# microcontrollerOptical.net
KiCad netlist of a schematic drawn in Altium Designer
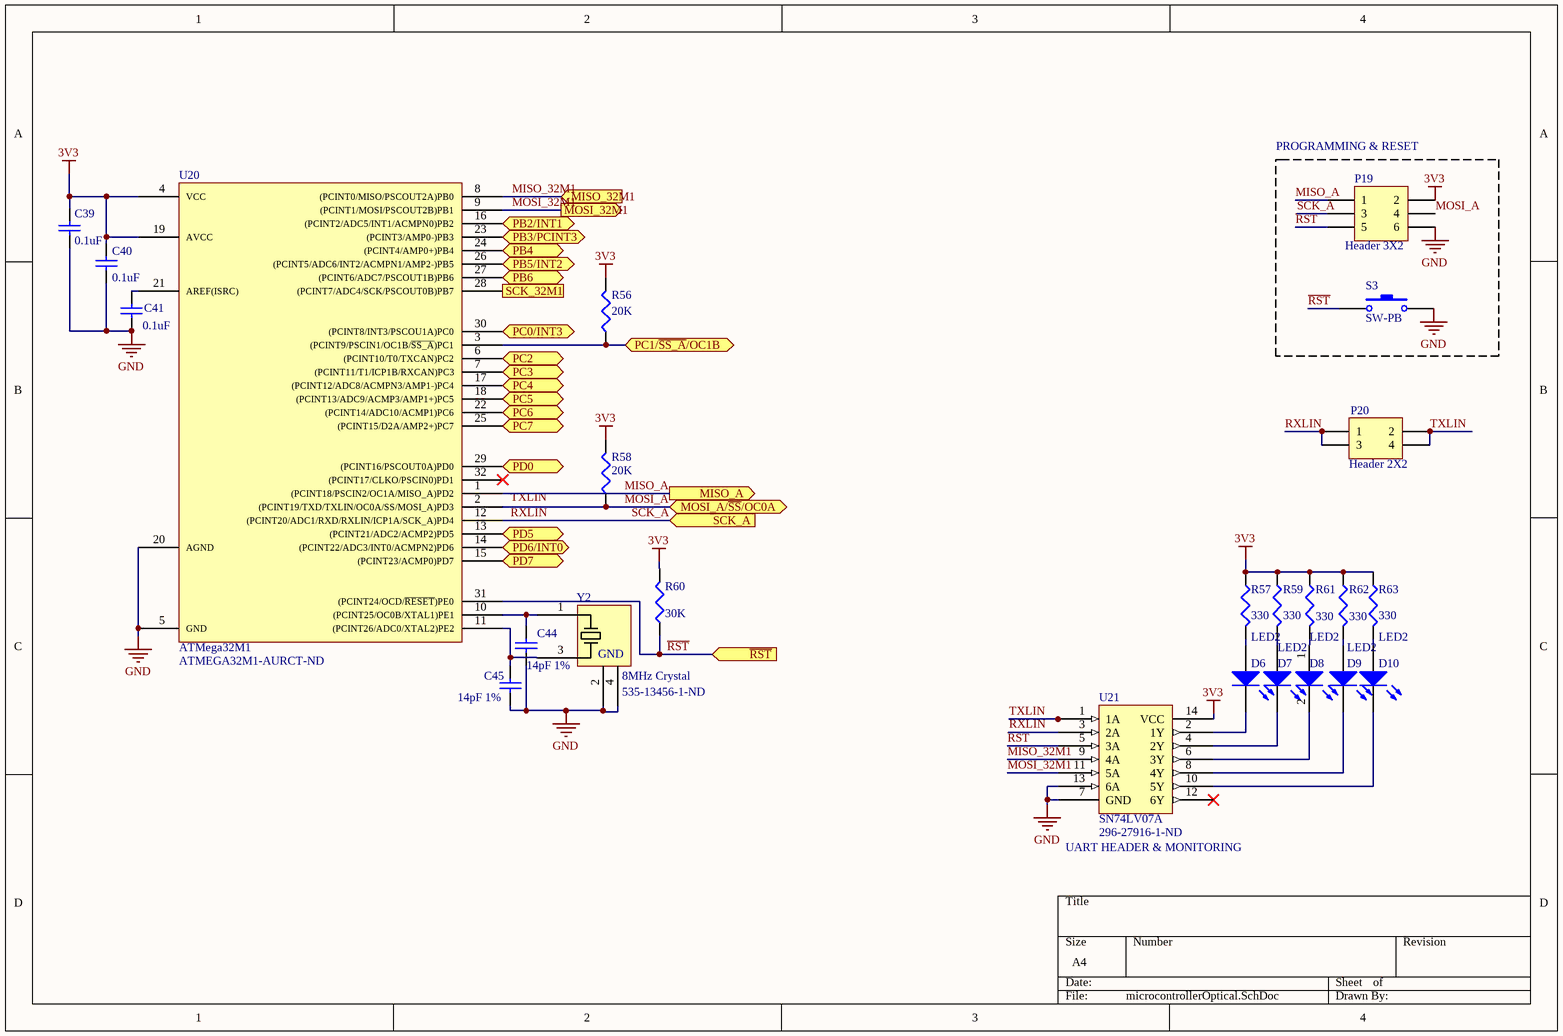
[diagram p0: microcontrollerOptical.SchDoc]

(export (version "E")
  (design (tool "Eeschema 10.0.6"))
  (components
    (comp (ref "C39")
      (value "0.1uF")
      (footprint "1608[0603]")
      (description "Capacitor (Semiconductor SIM Model)")
      (fields (field (name "PUBLISHER") "Altium Limited"))
      (libsource (lib "Miscellaneous Devices") (part "Cap Semi"))
    )
    (comp (ref "C40")
      (value "0.1uF")
      (footprint "1608[0603]")
      (description "Capacitor (Semiconductor SIM Model)")
      (fields (field (name "PUBLISHER") "Altium Limited"))
      (libsource (lib "Miscellaneous Devices") (part "Cap Semi"))
    )
    (comp (ref "C41")
      (value "0.1uF")
      (footprint "1608[0603]")
      (description "Capacitor (Semiconductor SIM Model)")
      (fields (field (name "PUBLISHER") "Altium Limited"))
      (libsource (lib "Miscellaneous Devices") (part "Cap Semi"))
    )
    (comp (ref "C44")
      (value "14pF 1%")
      (footprint "1608[0603]")
      (description "Capacitor (Semiconductor SIM Model)")
      (fields (field (name "Comment") "15pF 1%") (field (name "PUBLISHER") "Altium Limited"))
      (libsource (lib "Miscellaneous Devices") (part "Cap Semi"))
    )
    (comp (ref "C45")
      (value "14pF 1%")
      (footprint "1608[0603]")
      (description "Capacitor (Semiconductor SIM Model)")
      (fields (field (name "Comment") "15pF 1%") (field (name "PUBLISHER") "Altium Limited"))
      (libsource (lib "Miscellaneous Devices") (part "Cap Semi"))
    )
    (comp (ref "D6")
      (value "LED2")
      (footprint "0603-LED")
      (description "Typical RED, GREEN, YELLOW, AMBER GaAs LED")
      (fields (field (name "PUBLISHER") "Altium Limited"))
      (libsource (lib "Miscellaneous Devices") (part "LED2"))
    )
    (comp (ref "D7")
      (value "LED2")
      (footprint "0603-LED")
      (description "Typical RED, GREEN, YELLOW, AMBER GaAs LED")
      (fields (field (name "PUBLISHER") "Altium Limited"))
      (libsource (lib "Miscellaneous Devices") (part "LED2"))
    )
    (comp (ref "D8")
      (value "LED2")
      (footprint "0603-LED")
      (description "Typical RED, GREEN, YELLOW, AMBER GaAs LED")
      (fields (field (name "PUBLISHER") "Altium Limited"))
      (libsource (lib "") (part "LED2_1"))
    )
    (comp (ref "D9")
      (value "LED2")
      (footprint "0603-LED")
      (description "Typical RED, GREEN, YELLOW, AMBER GaAs LED")
      (fields (field (name "PUBLISHER") "Altium Limited"))
      (libsource (lib "Miscellaneous Devices") (part "LED2"))
    )
    (comp (ref "D10")
      (value "LED2")
      (footprint "0603-LED")
      (description "Typical RED, GREEN, YELLOW, AMBER GaAs LED")
      (fields (field (name "PUBLISHER") "Altium Limited"))
      (libsource (lib "Miscellaneous Devices") (part "LED2"))
    )
    (comp (ref "P19")
      (value "Header 3X2")
      (footprint "HDR2X3")
      (description "Header, 3-Pin, Dual row")
      (fields (field (name "PUBLISHER") "Altium Limited"))
      (libsource (lib "Miscellaneous Connectors") (part "Header 3X2"))
    )
    (comp (ref "P20")
      (value "Header 2X2")
      (footprint "HDR2X2")
      (description "Header, 2-Pin, Dual row")
      (fields (field (name "PUBLISHER") "Altium Limited"))
      (libsource (lib "Miscellaneous Connectors") (part "Header 2X2"))
    )
    (comp (ref "R56")
      (value "20K")
      (footprint "J1-0603")
      (description "Resistor")
      (fields (field (name "PUBLISHER") "Altium Limited"))
      (libsource (lib "Miscellaneous Devices") (part "Res3"))
    )
    (comp (ref "R57")
      (value "330")
      (footprint "J1-0603")
      (description "Resistor")
      (fields (field (name "PUBLISHER") "Altium Limited"))
      (libsource (lib "Miscellaneous Devices") (part "Res3"))
    )
    (comp (ref "R58")
      (value "20K")
      (footprint "J1-0603")
      (description "Resistor")
      (fields (field (name "PUBLISHER") "Altium Limited"))
      (libsource (lib "Miscellaneous Devices") (part "Res3"))
    )
    (comp (ref "R59")
      (value "330")
      (footprint "J1-0603")
      (description "Resistor")
      (fields (field (name "PUBLISHER") "Altium Limited"))
      (libsource (lib "Miscellaneous Devices") (part "Res3"))
    )
    (comp (ref "R60")
      (value "30K")
      (footprint "J1-0603")
      (description "Resistor")
      (fields (field (name "PUBLISHER") "Altium Limited"))
      (libsource (lib "Miscellaneous Devices") (part "Res3"))
    )
    (comp (ref "R61")
      (value "330")
      (footprint "J1-0603")
      (description "Resistor")
      (fields (field (name "PUBLISHER") "Altium Limited"))
      (libsource (lib "Miscellaneous Devices") (part "Res3"))
    )
    (comp (ref "R62")
      (value "330")
      (footprint "J1-0603")
      (description "Resistor")
      (fields (field (name "PUBLISHER") "Altium Limited"))
      (libsource (lib "Miscellaneous Devices") (part "Res3"))
    )
    (comp (ref "R63")
      (value "330")
      (footprint "J1-0603")
      (description "Resistor")
      (fields (field (name "PUBLISHER") "Altium Limited"))
      (libsource (lib "Miscellaneous Devices") (part "Res3"))
    )
    (comp (ref "S3")
      (value "SW-PB")
      (footprint "Pushbutton")
      (description "Switch")
      (fields (field (name "PUBLISHER") "Altium Limited"))
      (libsource (lib "Miscellaneous Devices") (part "SW-PB"))
    )
    (comp (ref "U20")
      (value "ATMega32M1")
      (footprint "QFP80P900X900X120-32N")
      (description "Atmel 8-bit AVR microcontroller.")
      (fields (field (name "SUPPLIER PART NUMBER 1") "ATMEGA32M1-AURCT-ND"))
      (libsource (lib "ICs") (part "ATMega32M1"))
    )
    (comp (ref "U21")
      (value "SN74LV07A")
      (footprint "SOP65P640X120-14N")
      (description "Six element 1-bit non-inverting open-drain buffer.")
      (fields (field (name "SUPPLIER PART NUMBER") "296-27916-1-ND"))
      (libsource (lib "ICs") (part "SN74LV07A"))
    )
    (comp (ref "Y2")
      (value "8MHz Crystal")
      (footprint "OSCSC500X320X110-4N")
      (description "8MHz Abracom 4-pin crystal.")
      (fields (field (name "SUPPLIER PART NUMBER 1") "535-13456-1-ND"))
      (libsource (lib "ICs") (part "8MHz Abracom 4-Pin Crystal"))
    )
  )
  (nets
    (net (code "1") (name "/MISO_32M1") (class "Default")
      (node (ref "U20") (pin "8") (pinfunction "(PCINT0/MISO/PSCOUT2A)PB0_8") (pintype "passive"))
      (node (ref "U21") (pin "9") (pinfunction "4A_9") (pintype "input"))
    )
    (net (code "2") (name "/MISO_A") (class "Default")
      (node (ref "P19") (pin "1") (pinfunction "1_1") (pintype "passive"))
      (node (ref "U20") (pin "1") (pinfunction "(PCINT18/PSCIN2/OC1A/MISO_A)PD2_1") (pintype "passive"))
    )
    (net (code "3") (name "/MOSI_32M1") (class "Default")
      (node (ref "U20") (pin "9") (pinfunction "(PCINT1/MOSI/PSCOUT2B)PB1_9") (pintype "passive"))
      (node (ref "U21") (pin "11") (pinfunction "5A_11") (pintype "input"))
    )
    (net (code "4") (name "/MOSI_A") (class "Default")
      (node (ref "P19") (pin "4") (pinfunction "4_4") (pintype "passive"))
      (node (ref "R58") (pin "1") (pinfunction "1_1") (pintype "passive"))
      (node (ref "U20") (pin "2") (pinfunction "(PCINT19/TXD/TXLIN/OC0A/SS/MOSI_A)PD3_2") (pintype "passive"))
    )
    (net (code "5") (name "/PB2{slash}INT1") (class "Default")
      (node (ref "U20") (pin "16") (pinfunction "(PCINT2/ADC5/INT1/ACMPN0)PB2_16") (pintype "passive"))
    )
    (net (code "6") (name "/PB3{slash}PCINT3") (class "Default")
      (node (ref "U20") (pin "23") (pinfunction "(PCINT3/AMP0-)PB3_23") (pintype "passive"))
    )
    (net (code "7") (name "/PB4") (class "Default")
      (node (ref "U20") (pin "24") (pinfunction "(PCINT4/AMP0+)PB4_24") (pintype "passive"))
    )
    (net (code "8") (name "/PB5{slash}INT2") (class "Default")
      (node (ref "U20") (pin "26") (pinfunction "(PCINT5/ADC6/INT2/ACMPN1/AMP2-)PB5_26") (pintype "passive"))
    )
    (net (code "9") (name "/PB6") (class "Default")
      (node (ref "U20") (pin "27") (pinfunction "(PCINT6/ADC7/PSCOUT1B)PB6_27") (pintype "passive"))
    )
    (net (code "10") (name "/PC0{slash}INT3") (class "Default")
      (node (ref "U20") (pin "30") (pinfunction "(PCINT8/INT3/PSCOU1A)PC0_30") (pintype "passive"))
    )
    (net (code "11") (name "/PC1{slash}~{SS_A}{slash}OC1B") (class "Default")
      (node (ref "R56") (pin "1") (pinfunction "1_1") (pintype "passive"))
      (node (ref "U20") (pin "3") (pinfunction "(PCINT9/PSCIN1/OC1B/~{SS_A})PC1_3") (pintype "passive"))
    )
    (net (code "12") (name "/PC2") (class "Default")
      (node (ref "U20") (pin "6") (pinfunction "(PCINT10/T0/TXCAN)PC2_6") (pintype "passive"))
    )
    (net (code "13") (name "/PC3") (class "Default")
      (node (ref "U20") (pin "7") (pinfunction "(PCINT11/T1/ICP1B/RXCAN)PC3_7") (pintype "passive"))
    )
    (net (code "14") (name "/PC4") (class "Default")
      (node (ref "U20") (pin "17") (pinfunction "(PCINT12/ADC8/ACMPN3/AMP1-)PC4_17") (pintype "passive"))
    )
    (net (code "15") (name "/PC5") (class "Default")
      (node (ref "U20") (pin "18") (pinfunction "(PCINT13/ADC9/ACMP3/AMP1+)PC5_18") (pintype "passive"))
    )
    (net (code "16") (name "/PC6") (class "Default")
      (node (ref "U20") (pin "22") (pinfunction "(PCINT14/ADC10/ACMP1)PC6_22") (pintype "passive"))
    )
    (net (code "17") (name "/PC7") (class "Default")
      (node (ref "U20") (pin "25") (pinfunction "(PCINT15/D2A/AMP2+)PC7_25") (pintype "passive"))
    )
    (net (code "18") (name "/PD0") (class "Default")
      (node (ref "U20") (pin "29") (pinfunction "(PCINT16/PSCOUT0A)PD0_29") (pintype "passive"))
    )
    (net (code "19") (name "/PD5") (class "Default")
      (node (ref "U20") (pin "13") (pinfunction "(PCINT21/ADC2/ACMP2)PD5_13") (pintype "passive"))
    )
    (net (code "20") (name "/PD6{slash}INT0") (class "Default")
      (node (ref "U20") (pin "14") (pinfunction "(PCINT22/ADC3/INT0/ACMPN2)PD6_14") (pintype "passive"))
    )
    (net (code "21") (name "/PD7") (class "Default")
      (node (ref "U20") (pin "15") (pinfunction "(PCINT23/ACMP0)PD7_15") (pintype "passive"))
    )
    (net (code "22") (name "/RXLIN") (class "Default")
      (node (ref "P19") (pin "3") (pinfunction "3_3") (pintype "passive"))
      (node (ref "P20") (pin "1") (pinfunction "1_1") (pintype "passive"))
      (node (ref "P20") (pin "3") (pinfunction "3_3") (pintype "passive"))
      (node (ref "U20") (pin "12") (pinfunction "(PCINT20/ADC1/RXD/RXLIN/ICP1A/SCK_A)PD4_12") (pintype "passive"))
      (node (ref "U21") (pin "3") (pinfunction "2A_3") (pintype "input"))
    )
    (net (code "23") (name "/SCK_32M1") (class "Default")
      (node (ref "U20") (pin "28") (pinfunction "(PCINT7/ADC4/SCK/PSCOUT0B)PB7_28") (pintype "passive"))
    )
    (net (code "24") (name "/TXLIN") (class "Default")
      (node (ref "P20") (pin "2") (pinfunction "2_2") (pintype "passive"))
      (node (ref "P20") (pin "4") (pinfunction "4_4") (pintype "passive"))
      (node (ref "U21") (pin "1") (pinfunction "1A_1") (pintype "input"))
    )
    (net (code "25") (name "/~{RST}") (class "Default")
      (node (ref "P19") (pin "5") (pinfunction "5_5") (pintype "passive"))
      (node (ref "R60") (pin "1") (pinfunction "1_1") (pintype "passive"))
      (node (ref "S3") (pin "1") (pinfunction "1_1") (pintype "passive"))
      (node (ref "U20") (pin "31") (pinfunction "(PCINT24/OCD/~{RESET})PE0_31") (pintype "passive"))
      (node (ref "U21") (pin "5") (pinfunction "3A_5") (pintype "input"))
    )
    (net (code "26") (name "3V3") (class "Default")
      (node (ref "C39") (pin "2") (pinfunction "2_2") (pintype "passive"))
      (node (ref "C40") (pin "2") (pinfunction "2_2") (pintype "passive"))
      (node (ref "P19") (pin "2") (pinfunction "2_2") (pintype "passive"))
      (node (ref "R56") (pin "2") (pinfunction "2_2") (pintype "passive"))
      (node (ref "R57") (pin "1") (pinfunction "1_1") (pintype "passive"))
      (node (ref "R58") (pin "2") (pinfunction "2_2") (pintype "passive"))
      (node (ref "R59") (pin "1") (pinfunction "1_1") (pintype "passive"))
      (node (ref "R60") (pin "2") (pinfunction "2_2") (pintype "passive"))
      (node (ref "R61") (pin "1") (pinfunction "1_1") (pintype "passive"))
      (node (ref "R62") (pin "1") (pinfunction "1_1") (pintype "passive"))
      (node (ref "R63") (pin "1") (pinfunction "1_1") (pintype "passive"))
      (node (ref "U20") (pin "19") (pinfunction "AVCC_19") (pintype "passive"))
      (node (ref "U20") (pin "4") (pinfunction "VCC_4") (pintype "passive"))
      (node (ref "U21") (pin "14") (pinfunction "VCC_14") (pintype "power_in"))
    )
    (net (code "27") (name "GND") (class "Default")
      (node (ref "C39") (pin "1") (pinfunction "1_1") (pintype "passive"))
      (node (ref "C40") (pin "1") (pinfunction "1_1") (pintype "passive"))
      (node (ref "C41") (pin "2") (pinfunction "2_2") (pintype "passive"))
      (node (ref "C44") (pin "1") (pinfunction "1_1") (pintype "passive"))
      (node (ref "C45") (pin "1") (pinfunction "1_1") (pintype "passive"))
      (node (ref "P19") (pin "6") (pinfunction "6_6") (pintype "passive"))
      (node (ref "S3") (pin "2") (pinfunction "2_2") (pintype "passive"))
      (node (ref "U20") (pin "20") (pinfunction "AGND_20") (pintype "passive"))
      (node (ref "U20") (pin "5") (pinfunction "GND_5") (pintype "passive"))
      (node (ref "U21") (pin "13") (pinfunction "6A_13") (pintype "input"))
      (node (ref "U21") (pin "7") (pinfunction "GND_7") (pintype "power_in"))
      (node (ref "Y2") (pin "2") (pinfunction "5_2") (pintype "passive"))
      (node (ref "Y2") (pin "4") (pinfunction "4_4") (pintype "passive"))
    )
    (net (code "28") (name "Net-(D6-A)") (class "Default")
      (node (ref "D6") (pin "1") (pinfunction "A_1") (pintype "passive"))
      (node (ref "R57") (pin "2") (pinfunction "2_2") (pintype "passive"))
    )
    (net (code "29") (name "Net-(D6-K)") (class "Default")
      (node (ref "D6") (pin "2") (pinfunction "K_2") (pintype "passive"))
      (node (ref "U21") (pin "2") (pinfunction "1Y_2") (pintype "output"))
    )
    (net (code "30") (name "Net-(D7-A)") (class "Default")
      (node (ref "D7") (pin "1") (pinfunction "A_1") (pintype "passive"))
      (node (ref "R59") (pin "2") (pinfunction "2_2") (pintype "passive"))
    )
    (net (code "31") (name "Net-(D7-K)") (class "Default")
      (node (ref "D7") (pin "2") (pinfunction "K_2") (pintype "passive"))
      (node (ref "U21") (pin "4") (pinfunction "2Y_4") (pintype "output"))
    )
    (net (code "32") (name "Net-(D8-A)") (class "Default")
      (node (ref "D8") (pin "1") (pinfunction "A_1") (pintype "passive"))
      (node (ref "R61") (pin "2") (pinfunction "2_2") (pintype "passive"))
    )
    (net (code "33") (name "Net-(D8-K)") (class "Default")
      (node (ref "D8") (pin "2") (pinfunction "K_2") (pintype "passive"))
      (node (ref "U21") (pin "6") (pinfunction "3Y_6") (pintype "output"))
    )
    (net (code "34") (name "Net-(D9-A)") (class "Default")
      (node (ref "D9") (pin "1") (pinfunction "A_1") (pintype "passive"))
      (node (ref "R62") (pin "2") (pinfunction "2_2") (pintype "passive"))
    )
    (net (code "35") (name "Net-(D9-K)") (class "Default")
      (node (ref "D9") (pin "2") (pinfunction "K_2") (pintype "passive"))
      (node (ref "U21") (pin "8") (pinfunction "4Y_8") (pintype "output"))
    )
    (net (code "36") (name "Net-(D10-A)") (class "Default")
      (node (ref "D10") (pin "1") (pinfunction "A_1") (pintype "passive"))
      (node (ref "R63") (pin "2") (pinfunction "2_2") (pintype "passive"))
    )
    (net (code "37") (name "Net-(D10-K)") (class "Default")
      (node (ref "D10") (pin "2") (pinfunction "K_2") (pintype "passive"))
      (node (ref "U21") (pin "10") (pinfunction "5Y_10") (pintype "output"))
    )
    (net (code "38") (name "Net-(U20-(PCINT25{slash}OC0B{slash}XTAL1)PE1)") (class "Default")
      (node (ref "C44") (pin "2") (pinfunction "2_2") (pintype "passive"))
      (node (ref "U20") (pin "10") (pinfunction "(PCINT25/OC0B/XTAL1)PE1_10") (pintype "passive"))
      (node (ref "Y2") (pin "1") (pinfunction "IN_1") (pintype "passive"))
    )
    (net (code "39") (name "Net-(U20-(PCINT26{slash}ADC0{slash}XTAL2)PE2)") (class "Default")
      (node (ref "C45") (pin "2") (pinfunction "2_2") (pintype "passive"))
      (node (ref "U20") (pin "11") (pinfunction "(PCINT26/ADC0/XTAL2)PE2_11") (pintype "passive"))
      (node (ref "Y2") (pin "3") (pinfunction "IN_3") (pintype "passive"))
    )
    (net (code "40") (name "Net-(U20-AREF(ISRC))") (class "Default")
      (node (ref "C41") (pin "1") (pinfunction "1_1") (pintype "passive"))
      (node (ref "U20") (pin "21") (pinfunction "AREF(ISRC)_21") (pintype "passive"))
    )
    (net (code "41") (name "unconnected-(U20-(PCINT17{slash}CLKO{slash}PSCIN0)PD1-Pad32)") (class "Default")
      (node (ref "U20") (pin "32") (pinfunction "(PCINT17/CLKO/PSCIN0)PD1_32") (pintype "passive+no_connect"))
    )
    (net (code "42") (name "unconnected-(U21-6Y-Pad12)") (class "Default")
      (node (ref "U21") (pin "12") (pinfunction "6Y_12") (pintype "output"))
    )
  )
)
